# DK_POWER.net
KiCad netlist of a schematic drawn in Altium Designer
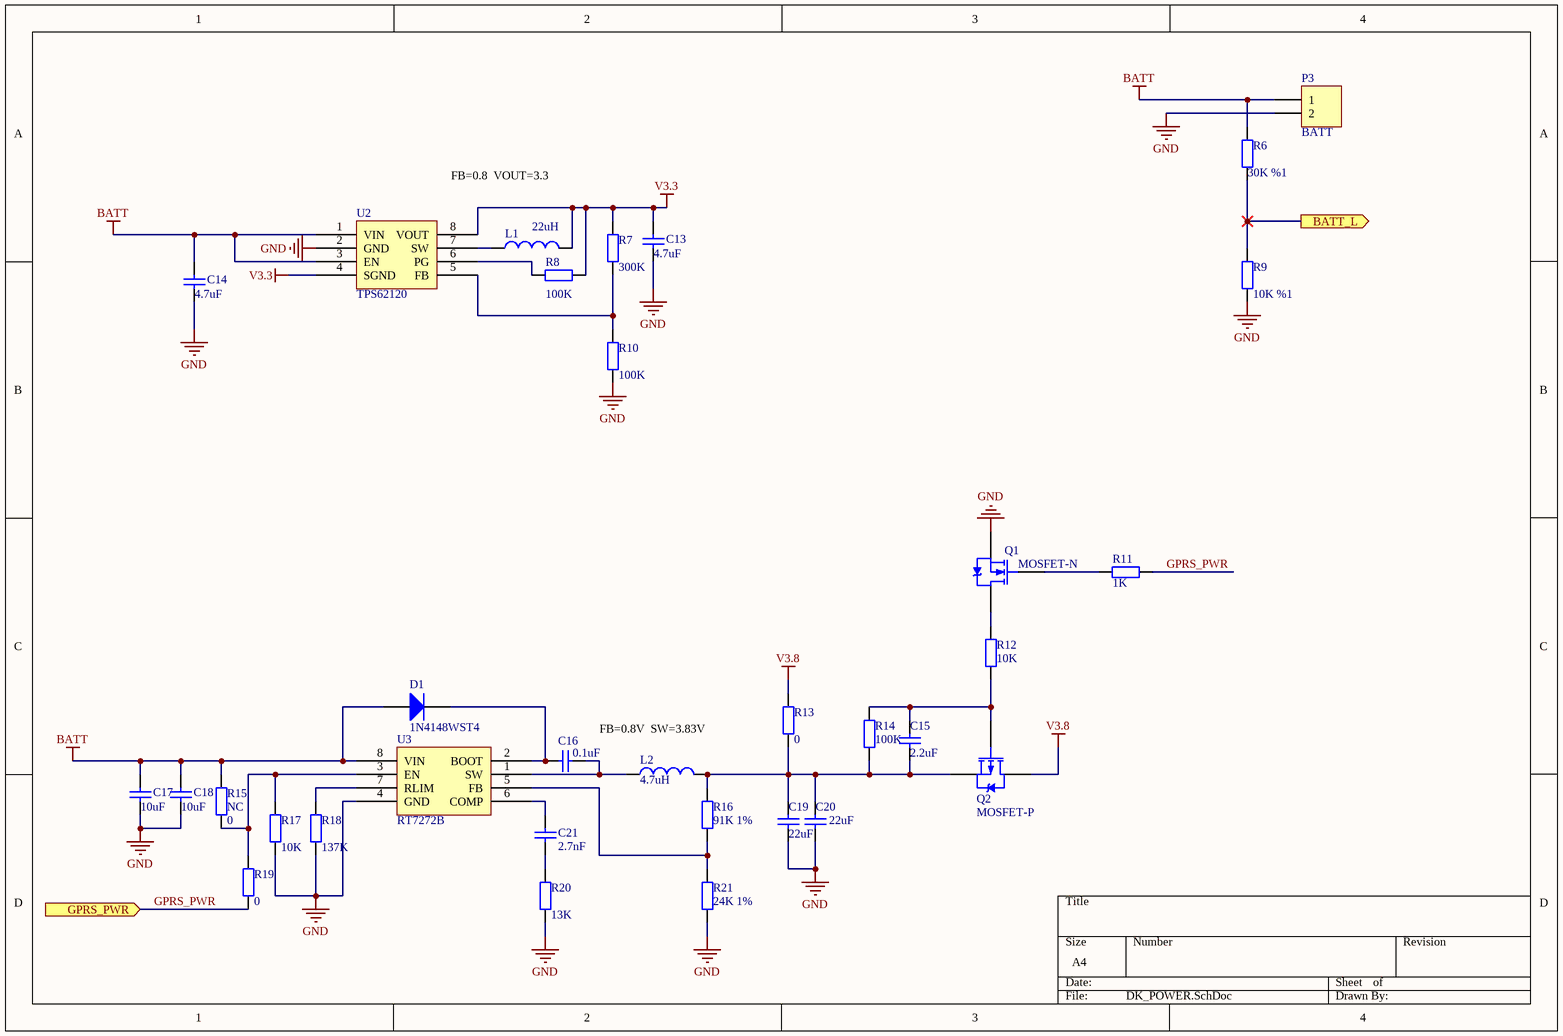
[diagram p0: DK_POWER.SchDoc]

(export (version "E")
  (design (tool "Eeschema 10.0.6"))
  (components
    (comp (ref "C13")
      (value "4.7uF")
      (footprint "0603")
      (description "Capacitor")
      (fields (field (name "Comment") "Cap") (field (name "PUBLISHER") "Altium Limited"))
      (libsource (lib "Miscellaneous Devices") (part "Cap"))
    )
    (comp (ref "C14")
      (value "4.7uF")
      (footprint "0603")
      (description "Capacitor")
      (fields (field (name "Comment") "Cap") (field (name "PUBLISHER") "Altium Limited"))
      (libsource (lib "Miscellaneous Devices") (part "Cap"))
    )
    (comp (ref "C15")
      (value "2.2uF")
      (footprint "0603")
      (description "Capacitor")
      (fields (field (name "Comment") "Cap") (field (name "PUBLISHER") "Altium Limited"))
      (libsource (lib "Miscellaneous Devices") (part "Cap"))
    )
    (comp (ref "C16")
      (value "0.1uF")
      (footprint "0603")
      (description "Capacitor")
      (fields (field (name "Comment") "Cap") (field (name "PUBLISHER") "Altium Limited"))
      (libsource (lib "Miscellaneous Devices") (part "Cap"))
    )
    (comp (ref "C17")
      (value "10uF")
      (footprint "0603")
      (description "Capacitor")
      (fields (field (name "Comment") "Cap") (field (name "PUBLISHER") "Altium Limited"))
      (libsource (lib "Miscellaneous Devices") (part "Cap"))
    )
    (comp (ref "C18")
      (value "10uF")
      (footprint "0603")
      (description "Capacitor")
      (fields (field (name "Comment") "Cap") (field (name "PUBLISHER") "Altium Limited"))
      (libsource (lib "Miscellaneous Devices") (part "Cap"))
    )
    (comp (ref "C19")
      (value "22uF")
      (footprint "0603")
      (description "Capacitor")
      (fields (field (name "Comment") "Cap") (field (name "PUBLISHER") "Altium Limited"))
      (libsource (lib "Miscellaneous Devices") (part "Cap"))
    )
    (comp (ref "C20")
      (value "22uF")
      (footprint "0603")
      (description "Capacitor")
      (fields (field (name "Comment") "Cap") (field (name "PUBLISHER") "Altium Limited"))
      (libsource (lib "Miscellaneous Devices") (part "Cap"))
    )
    (comp (ref "C21")
      (value "2.7nF")
      (footprint "0603")
      (description "Capacitor")
      (fields (field (name "Comment") "Cap") (field (name "PUBLISHER") "Altium Limited"))
      (libsource (lib "Miscellaneous Devices") (part "Cap"))
    )
    (comp (ref "D1")
      (value "1N4148WST4")
      (footprint "SOD-323")
      (description "Default Diode")
      (fields (field (name "PUBLISHER") "Altium Limited"))
      (libsource (lib "Miscellaneous Devices") (part "Diode"))
    )
    (comp (ref "L1")
      (value "22uH")
      (footprint "0630")
      (description "Inductor")
      (fields (field (name "PUBLISHER") "Altium Limited"))
      (libsource (lib "Miscellaneous Devices") (part "Inductor"))
    )
    (comp (ref "L2")
      (value "4.7uH")
      (footprint "0630")
      (description "Inductor")
      (fields (field (name "PUBLISHER") "Altium Limited"))
      (libsource (lib "Miscellaneous Devices") (part "Inductor"))
    )
    (comp (ref "P3")
      (value "BATT")
      (footprint "HEAD2L-0.8")
      (description "Header, 2-Pin")
      (fields (field (name "PUBLISHER") "Altium Limited"))
      (libsource (lib "Miscellaneous Connectors") (part "Header 2"))
    )
    (comp (ref "Q1")
      (value "MOSFET-N")
      (footprint "SOT-23A")
      (description "N-Channel Power MOSFET")
      (fields (field (name "PUBLISHER") "Altium Limited"))
      (libsource (lib "Miscellaneous Devices") (part "NMOS-2"))
    )
    (comp (ref "Q2")
      (value "MOSFET-P")
      (footprint "SOT-23A")
      (description "P-Channel Power MOSFET")
      (fields (field (name "PUBLISHER") "Altium Limited"))
      (libsource (lib "Miscellaneous Devices") (part "PMOS-2"))
    )
    (comp (ref "R6")
      (value "30K %1")
      (footprint "0603")
      (description "Resistor")
      (fields (field (name "Comment") "Res2") (field (name "PUBLISHER") "Altium Limited"))
      (libsource (lib "") (part "Res2_1"))
    )
    (comp (ref "R7")
      (value "300K")
      (footprint "0603")
      (description "Resistor")
      (fields (field (name "Comment") "Res2") (field (name "PUBLISHER") "Altium Limited"))
      (libsource (lib "") (part "Res2_1"))
    )
    (comp (ref "R8")
      (value "100K")
      (footprint "0603")
      (description "Resistor")
      (fields (field (name "Comment") "Res2") (field (name "PUBLISHER") "Altium Limited"))
      (libsource (lib "Miscellaneous Devices") (part "Res2"))
    )
    (comp (ref "R9")
      (value "10K %1")
      (footprint "0603")
      (description "Resistor")
      (fields (field (name "Comment") "Res2") (field (name "PUBLISHER") "Altium Limited"))
      (libsource (lib "") (part "Res2_2"))
    )
    (comp (ref "R10")
      (value "100K")
      (footprint "0603")
      (description "Resistor")
      (fields (field (name "Comment") "Res2") (field (name "PUBLISHER") "Altium Limited"))
      (libsource (lib "") (part "Res2_1"))
    )
    (comp (ref "R11")
      (value "1K")
      (footprint "0603")
      (description "Resistor")
      (fields (field (name "Comment") "Res2") (field (name "PUBLISHER") "Altium Limited"))
      (libsource (lib "Miscellaneous Devices") (part "Res2"))
    )
    (comp (ref "R12")
      (value "10K")
      (footprint "0603")
      (description "Resistor")
      (fields (field (name "Comment") "Res2") (field (name "PUBLISHER") "Altium Limited"))
      (libsource (lib "") (part "Res2_1"))
    )
    (comp (ref "R13")
      (value "0")
      (footprint "0603")
      (description "Resistor")
      (fields (field (name "Comment") "NC") (field (name "PUBLISHER") "Altium Limited"))
      (libsource (lib "") (part "Res2_1"))
    )
    (comp (ref "R14")
      (value "100K")
      (footprint "0603")
      (description "Resistor")
      (fields (field (name "Comment") "Res2") (field (name "PUBLISHER") "Altium Limited"))
      (libsource (lib "") (part "Res2_1"))
    )
    (comp (ref "R15")
      (value "NC")
      (footprint "0603")
      (description "Resistor")
      (fields (field (name "ALTIUM_VALUE") "0") (field (name "PUBLISHER") "Altium Limited"))
      (libsource (lib "") (part "Res2_1"))
    )
    (comp (ref "R16")
      (value "91K 1%")
      (footprint "0603")
      (description "Resistor")
      (fields (field (name "Comment") "Res2") (field (name "PUBLISHER") "Altium Limited"))
      (libsource (lib "") (part "Res2_1"))
    )
    (comp (ref "R17")
      (value "10K")
      (footprint "0603")
      (description "Resistor")
      (fields (field (name "Comment") "Res2") (field (name "PUBLISHER") "Altium Limited"))
      (libsource (lib "") (part "Res2_1"))
    )
    (comp (ref "R18")
      (value "137K")
      (footprint "0603")
      (description "Resistor")
      (fields (field (name "Comment") "Res2") (field (name "PUBLISHER") "Altium Limited"))
      (libsource (lib "") (part "Res2_1"))
    )
    (comp (ref "R19")
      (value "0")
      (footprint "0603")
      (description "Resistor")
      (fields (field (name "Comment") "Res2") (field (name "PUBLISHER") "Altium Limited"))
      (libsource (lib "") (part "Res2_1"))
    )
    (comp (ref "R20")
      (value "13K")
      (footprint "0603")
      (description "Resistor")
      (fields (field (name "Comment") "Res2") (field (name "PUBLISHER") "Altium Limited"))
      (libsource (lib "") (part "Res2_1"))
    )
    (comp (ref "R21")
      (value "24K 1%")
      (footprint "0603")
      (description "Resistor")
      (fields (field (name "Comment") "Res2") (field (name "PUBLISHER") "Altium Limited"))
      (libsource (lib "") (part "Res2_1"))
    )
    (comp (ref "U2") (value "TPS62120") (footprint "TPS62120") (libsource (lib "TPS62120") (part "TPS62120")))
    (comp (ref "U3") (value "RT7272B") (footprint "RT7272B") (libsource (lib "RT7272B") (part "RT7272B")))
  )
  (nets
    (net (code "1") (name "/BATT_L") (class "Default")
      (node (ref "R6") (pin "1") (pinfunction "1_1") (pintype "passive"))
      (node (ref "R9") (pin "1") (pinfunction "1_1") (pintype "passive"))
    )
    (net (code "2") (name "/GPRS_PWR") (class "Default")
      (node (ref "R11") (pin "2") (pinfunction "2_2") (pintype "passive"))
      (node (ref "R19") (pin "1") (pinfunction "1_1") (pintype "passive"))
    )
    (net (code "3") (name "BATT") (class "Default")
      (node (ref "C14") (pin "2") (pinfunction "2_2") (pintype "passive"))
      (node (ref "C17") (pin "2") (pinfunction "2_2") (pintype "passive"))
      (node (ref "C18") (pin "2") (pinfunction "2_2") (pintype "passive"))
      (node (ref "D1") (pin "1") (pinfunction "A_1") (pintype "passive"))
      (node (ref "P3") (pin "1") (pinfunction "1_1") (pintype "passive"))
      (node (ref "R15") (pin "2") (pinfunction "2_2") (pintype "passive"))
      (node (ref "R6") (pin "2") (pinfunction "2_2") (pintype "passive"))
      (node (ref "U2") (pin "1") (pinfunction "VIN_1") (pintype "passive"))
      (node (ref "U2") (pin "3") (pinfunction "EN_3") (pintype "passive"))
      (node (ref "U3") (pin "8") (pinfunction "VIN_8") (pintype "passive"))
    )
    (net (code "4") (name "GND") (class "Default")
      (node (ref "C13") (pin "1") (pinfunction "1_1") (pintype "passive"))
      (node (ref "C14") (pin "1") (pinfunction "1_1") (pintype "passive"))
      (node (ref "C17") (pin "1") (pinfunction "1_1") (pintype "passive"))
      (node (ref "C18") (pin "1") (pinfunction "1_1") (pintype "passive"))
      (node (ref "C19") (pin "1") (pinfunction "1_1") (pintype "passive"))
      (node (ref "C20") (pin "1") (pinfunction "1_1") (pintype "passive"))
      (node (ref "P3") (pin "2") (pinfunction "2_2") (pintype "passive"))
      (node (ref "Q1") (pin "3") (pinfunction "S_3") (pintype "passive"))
      (node (ref "R10") (pin "1") (pinfunction "1_1") (pintype "passive"))
      (node (ref "R17") (pin "1") (pinfunction "1_1") (pintype "passive"))
      (node (ref "R18") (pin "1") (pinfunction "1_1") (pintype "passive"))
      (node (ref "R20") (pin "1") (pinfunction "1_1") (pintype "passive"))
      (node (ref "R21") (pin "1") (pinfunction "1_1") (pintype "passive"))
      (node (ref "R9") (pin "2") (pinfunction "2_2") (pintype "passive"))
      (node (ref "U2") (pin "2") (pinfunction "GND_2") (pintype "passive"))
      (node (ref "U3") (pin "4") (pinfunction "GND_4") (pintype "passive"))
    )
    (net (code "5") (name "Net-(C21-Pad2)") (class "Default")
      (node (ref "C21") (pin "2") (pinfunction "2_2") (pintype "passive"))
      (node (ref "R20") (pin "2") (pinfunction "2_2") (pintype "passive"))
    )
    (net (code "6") (name "Net-(D1-K)") (class "Default")
      (node (ref "C16") (pin "2") (pinfunction "2_2") (pintype "passive"))
      (node (ref "D1") (pin "2") (pinfunction "K_2") (pintype "passive"))
      (node (ref "U3") (pin "2") (pinfunction "BOOT_2") (pintype "passive"))
    )
    (net (code "7") (name "Net-(Q1-D)") (class "Default")
      (node (ref "Q1") (pin "2") (pinfunction "D_2") (pintype "passive"))
      (node (ref "R12") (pin "2") (pinfunction "2_2") (pintype "passive"))
    )
    (net (code "8") (name "Net-(Q1-G)") (class "Default")
      (node (ref "Q1") (pin "1") (pinfunction "G_1") (pintype "passive"))
      (node (ref "R11") (pin "1") (pinfunction "1_1") (pintype "passive"))
    )
    (net (code "9") (name "Net-(Q2-G)") (class "Default")
      (node (ref "C15") (pin "2") (pinfunction "2_2") (pintype "passive"))
      (node (ref "Q2") (pin "1") (pinfunction "G_1") (pintype "passive"))
      (node (ref "R12") (pin "1") (pinfunction "1_1") (pintype "passive"))
      (node (ref "R14") (pin "2") (pinfunction "2_2") (pintype "passive"))
    )
    (net (code "10") (name "Net-(Q2-S)") (class "Default")
      (node (ref "C15") (pin "1") (pinfunction "1_1") (pintype "passive"))
      (node (ref "C19") (pin "2") (pinfunction "2_2") (pintype "passive"))
      (node (ref "C20") (pin "2") (pinfunction "2_2") (pintype "passive"))
      (node (ref "L2") (pin "2") (pinfunction "2_2") (pintype "passive"))
      (node (ref "Q2") (pin "3") (pinfunction "S_3") (pintype "passive"))
      (node (ref "R13") (pin "1") (pinfunction "1_1") (pintype "passive"))
      (node (ref "R14") (pin "1") (pinfunction "1_1") (pintype "passive"))
      (node (ref "R16") (pin "2") (pinfunction "2_2") (pintype "passive"))
    )
    (net (code "11") (name "Net-(U2-FB)") (class "Default")
      (node (ref "R10") (pin "2") (pinfunction "2_2") (pintype "passive"))
      (node (ref "R7") (pin "1") (pinfunction "1_1") (pintype "passive"))
      (node (ref "U2") (pin "5") (pinfunction "FB_5") (pintype "passive"))
    )
    (net (code "12") (name "Net-(U2-PG)") (class "Default")
      (node (ref "R8") (pin "1") (pinfunction "1_1") (pintype "passive"))
      (node (ref "U2") (pin "6") (pinfunction "PG_6") (pintype "passive"))
    )
    (net (code "13") (name "Net-(U2-SW)") (class "Default")
      (node (ref "L1") (pin "1") (pinfunction "1_1") (pintype "passive"))
      (node (ref "U2") (pin "7") (pinfunction "SW_7") (pintype "passive"))
    )
    (net (code "14") (name "Net-(U3-COMP)") (class "Default")
      (node (ref "C21") (pin "1") (pinfunction "1_1") (pintype "passive"))
      (node (ref "U3") (pin "6") (pinfunction "COMP_6") (pintype "passive"))
    )
    (net (code "15") (name "Net-(U3-EN)") (class "Default")
      (node (ref "R15") (pin "1") (pinfunction "1_1") (pintype "passive"))
      (node (ref "R17") (pin "2") (pinfunction "2_2") (pintype "passive"))
      (node (ref "R19") (pin "2") (pinfunction "2_2") (pintype "passive"))
      (node (ref "U3") (pin "3") (pinfunction "EN_3") (pintype "passive"))
    )
    (net (code "16") (name "Net-(U3-FB)") (class "Default")
      (node (ref "R16") (pin "1") (pinfunction "1_1") (pintype "passive"))
      (node (ref "R21") (pin "2") (pinfunction "2_2") (pintype "passive"))
      (node (ref "U3") (pin "5") (pinfunction "FB_5") (pintype "passive"))
    )
    (net (code "17") (name "Net-(U3-RLIM)") (class "Default")
      (node (ref "R18") (pin "2") (pinfunction "2_2") (pintype "passive"))
      (node (ref "U3") (pin "7") (pinfunction "RLIM_7") (pintype "passive"))
    )
    (net (code "18") (name "Net-(U3-SW)") (class "Default")
      (node (ref "C16") (pin "1") (pinfunction "1_1") (pintype "passive"))
      (node (ref "L2") (pin "1") (pinfunction "1_1") (pintype "passive"))
      (node (ref "U3") (pin "1") (pinfunction "SW_1") (pintype "passive"))
    )
    (net (code "19") (name "V3.3") (class "Default")
      (node (ref "C13") (pin "2") (pinfunction "2_2") (pintype "passive"))
      (node (ref "L1") (pin "2") (pinfunction "2_2") (pintype "passive"))
      (node (ref "R7") (pin "2") (pinfunction "2_2") (pintype "passive"))
      (node (ref "R8") (pin "2") (pinfunction "2_2") (pintype "passive"))
      (node (ref "U2") (pin "4") (pinfunction "SGND_4") (pintype "passive"))
      (node (ref "U2") (pin "8") (pinfunction "VOUT_8") (pintype "passive"))
    )
    (net (code "20") (name "V3.8") (class "Default")
      (node (ref "Q2") (pin "2") (pinfunction "D_2") (pintype "passive"))
      (node (ref "R13") (pin "2") (pinfunction "2_2") (pintype "passive"))
    )
  )
)
